# untitled.net
KiCad netlist of a schematic drawn in EAGLE
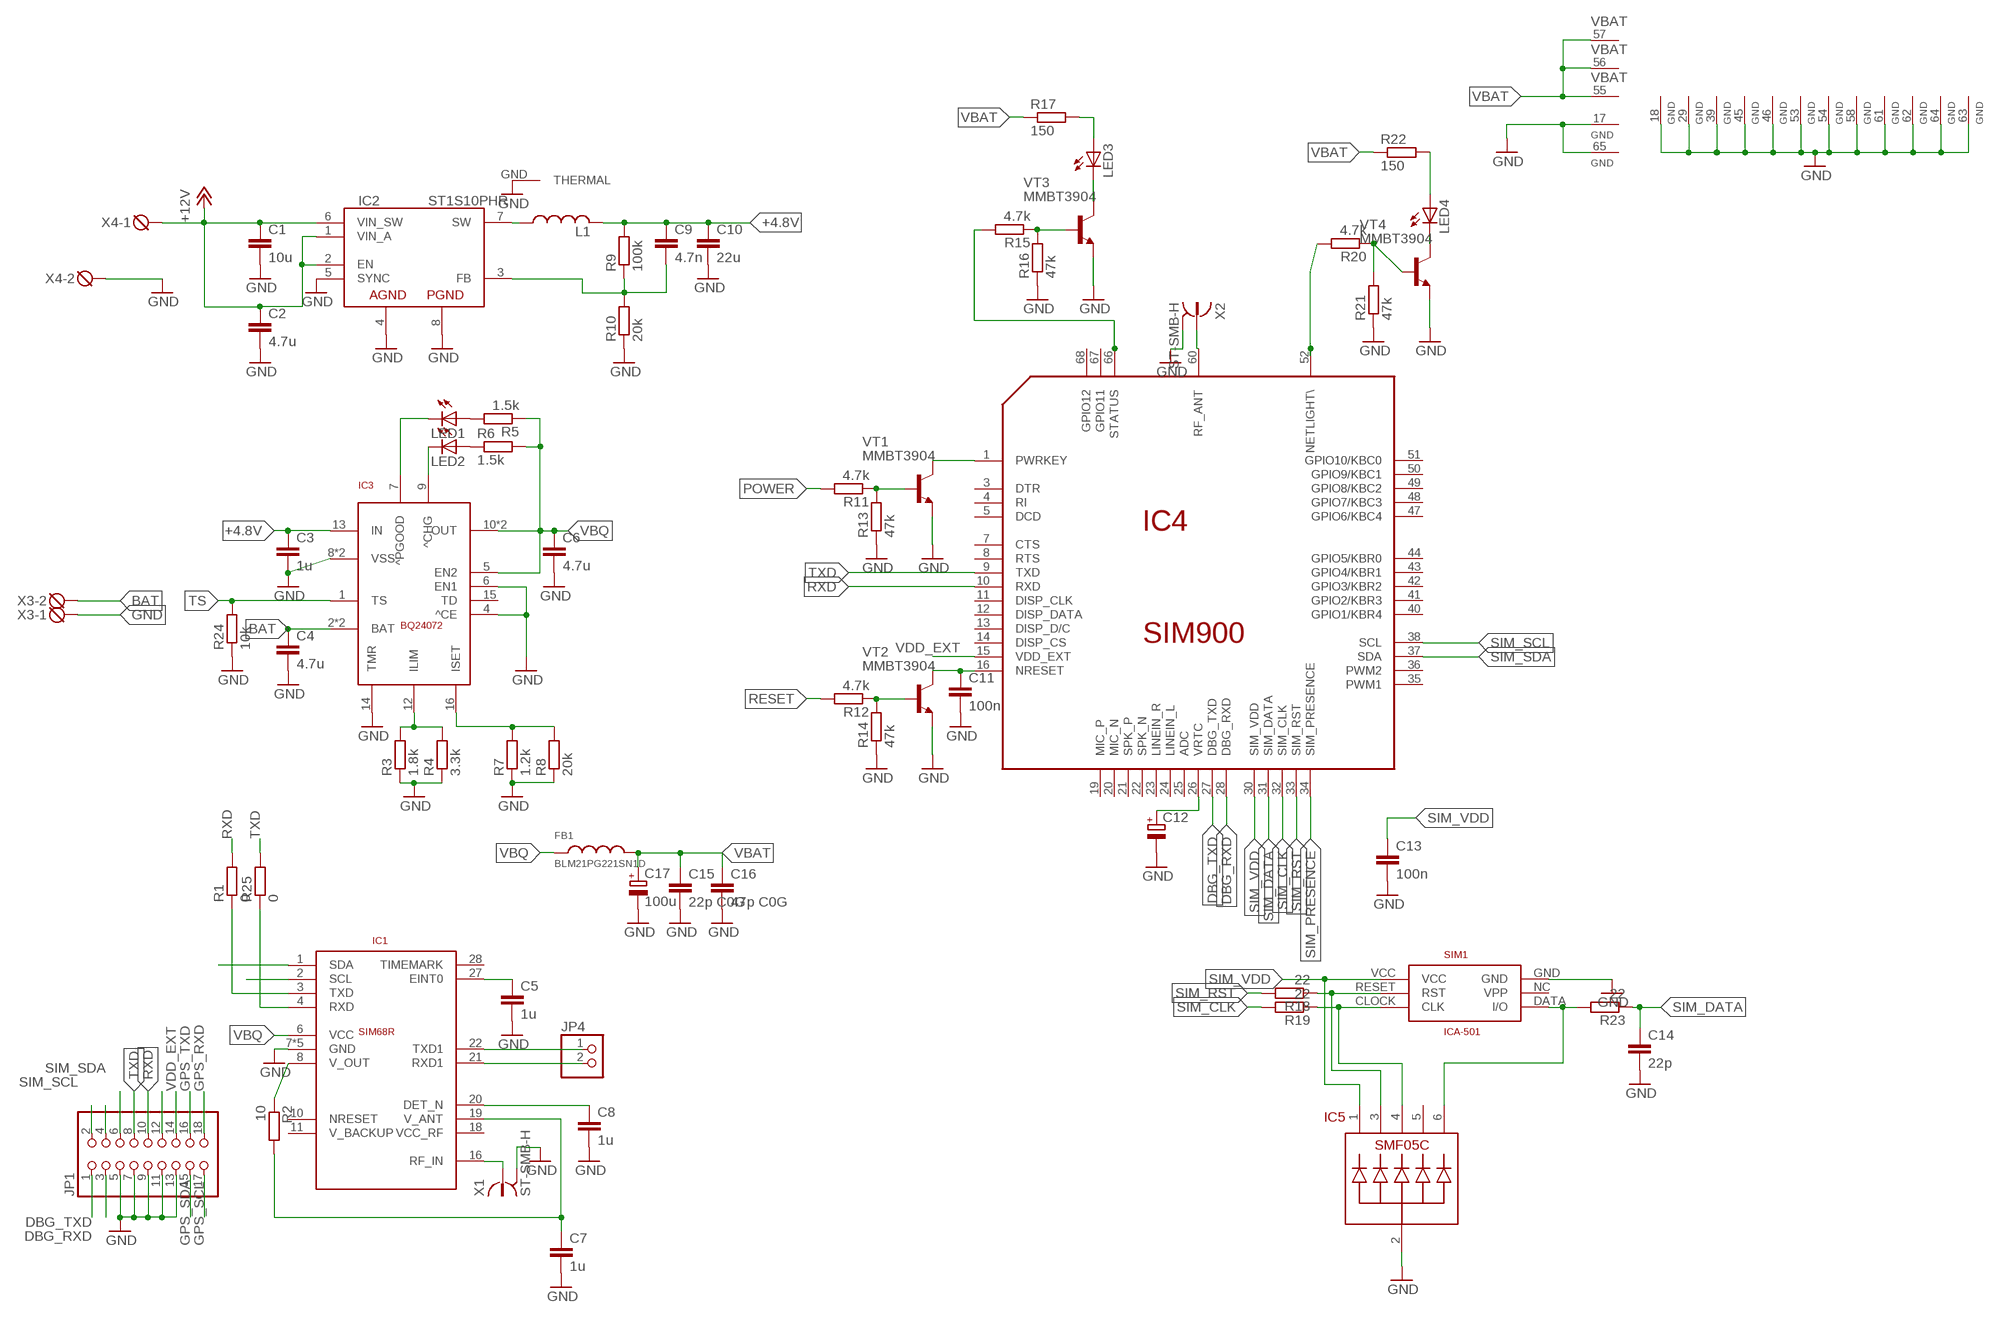
[diagram p0: schematic, sheet 1]

(export (version "E")
  (design (tool "Eeschema 10.0.6"))
  (components
    (comp (ref "C1")
      (value "10u")
      (footprint "eagle-import:C0805")
      (libsource (lib "eagle-import") (part "C-EUC0805"))
    )
    (comp (ref "C2")
      (value "4.7u")
      (footprint "eagle-import:C0805")
      (libsource (lib "eagle-import") (part "C-EUC0805"))
    )
    (comp (ref "C3")
      (value "1u")
      (footprint "eagle-import:C0805")
      (libsource (lib "eagle-import") (part "C-EUC0805"))
    )
    (comp (ref "C4")
      (value "4.7u")
      (footprint "eagle-import:C0805")
      (libsource (lib "eagle-import") (part "C-EUC0805"))
    )
    (comp (ref "C5")
      (value "1u")
      (footprint "eagle-import:C0805")
      (libsource (lib "eagle-import") (part "C-EUC0805"))
    )
    (comp (ref "C6")
      (value "4.7u")
      (footprint "eagle-import:C0805")
      (libsource (lib "eagle-import") (part "C-EUC0805"))
    )
    (comp (ref "C7")
      (value "1u")
      (footprint "eagle-import:C0805")
      (libsource (lib "eagle-import") (part "C-EUC0805"))
    )
    (comp (ref "C8")
      (value "1u")
      (footprint "eagle-import:C0805")
      (libsource (lib "eagle-import") (part "C-EUC0805"))
    )
    (comp (ref "C9")
      (value "4.7n")
      (footprint "eagle-import:C0805")
      (libsource (lib "eagle-import") (part "C-EUC0805"))
    )
    (comp (ref "C10")
      (value "22u")
      (footprint "eagle-import:C0805")
      (libsource (lib "eagle-import") (part "C-EUC0805"))
    )
    (comp (ref "C11")
      (value "100n")
      (footprint "eagle-import:C0805")
      (libsource (lib "eagle-import") (part "C-EUC0805"))
    )
    (comp (ref "C12")
      (value "CPOL-EUA/3216-18R")
      (footprint "eagle-import:A_3216-18R")
      (libsource (lib "eagle-import") (part "CPOL-EUA/3216-18R"))
    )
    (comp (ref "C13")
      (value "100n")
      (footprint "eagle-import:C0805")
      (libsource (lib "eagle-import") (part "C-EUC0805"))
    )
    (comp (ref "C14")
      (value "22p")
      (footprint "eagle-import:C0805")
      (libsource (lib "eagle-import") (part "C-EUC0805"))
    )
    (comp (ref "C15")
      (value "22p C0G")
      (footprint "eagle-import:C0805")
      (libsource (lib "eagle-import") (part "C-EUC0805"))
    )
    (comp (ref "C16")
      (value "47p C0G")
      (footprint "eagle-import:C0805")
      (libsource (lib "eagle-import") (part "C-EUC0805"))
    )
    (comp (ref "C17")
      (value "100u")
      (footprint "eagle-import:B_3528-21W")
      (libsource (lib "eagle-import") (part "CPOL-EUB/3528-21W"))
    )
    (comp (ref "FB1")
      (value "BLM21PG221SN1D")
      (footprint "eagle-import:R0805")
      (libsource (lib "eagle-import") (part "BLM21PG221"))
    )
    (comp (ref "IC1")
      (value "SIM68R")
      (footprint "eagle-import:SIM68")
      (libsource (lib "eagle-import") (part "SIM68R"))
    )
    (comp (ref "IC2")
      (value "ST1S10PHR")
      (footprint "eagle-import:HSOP8")
      (libsource (lib "eagle-import") (part "ST1S10PHR"))
    )
    (comp (ref "IC3")
      (value "BQ24072")
      (footprint "eagle-import:QFN16")
      (libsource (lib "eagle-import") (part "BQ24072"))
    )
    (comp (ref "IC4")
      (value "SIM900")
      (footprint "eagle-import:SIM900")
      (libsource (lib "eagle-import") (part "SIM900"))
    )
    (comp (ref "IC5")
      (value "SMF05C")
      (footprint "eagle-import:SC-70-6")
      (libsource (lib "eagle-import") (part "SMF05C"))
    )
    (comp (ref "JP1")
      (value "PINHD-2X9")
      (footprint "eagle-import:2X09")
      (libsource (lib "eagle-import") (part "PINHD-2X9"))
    )
    (comp (ref "JP4")
      (value "PINHD-1X2ROUND")
      (footprint "eagle-import:1X02ROUND")
      (libsource (lib "eagle-import") (part "PINHD-1X2ROUND"))
    )
    (comp (ref "L1")
      (value "INDUCTOR-SUMIDA-CDRH4D18")
      (footprint "eagle-import:INDUCTOR-SUMIDA-CDRH4D18")
      (libsource (lib "eagle-import") (part "INDUCTOR-SUMIDA-CDRH4D18"))
    )
    (comp (ref "LED1")
      (value "LED0805")
      (footprint "eagle-import:SML0805")
      (libsource (lib "eagle-import") (part "LED0805"))
    )
    (comp (ref "LED2")
      (value "LED0805")
      (footprint "eagle-import:SML0805")
      (libsource (lib "eagle-import") (part "LED0805"))
    )
    (comp (ref "LED3")
      (value "LED0805")
      (footprint "eagle-import:SML0805")
      (libsource (lib "eagle-import") (part "LED0805"))
    )
    (comp (ref "LED4")
      (value "LED0805")
      (footprint "eagle-import:SML0805")
      (libsource (lib "eagle-import") (part "LED0805"))
    )
    (comp (ref "R1")
      (value "0")
      (footprint "eagle-import:R0805")
      (libsource (lib "eagle-import") (part "R-EU_R0805"))
    )
    (comp (ref "R2")
      (value "10")
      (footprint "eagle-import:R0805")
      (libsource (lib "eagle-import") (part "R-EU_R0805"))
    )
    (comp (ref "R3")
      (value "1.8k")
      (footprint "eagle-import:R0805")
      (libsource (lib "eagle-import") (part "R-EU_R0805"))
    )
    (comp (ref "R4")
      (value "3.3k")
      (footprint "eagle-import:R0805")
      (libsource (lib "eagle-import") (part "R-EU_R0805"))
    )
    (comp (ref "R5")
      (value "1.5k")
      (footprint "eagle-import:R0603")
      (libsource (lib "eagle-import") (part "R-EU_R0603"))
    )
    (comp (ref "R6")
      (value "1.5k")
      (footprint "eagle-import:R0603")
      (libsource (lib "eagle-import") (part "R-EU_R0603"))
    )
    (comp (ref "R7")
      (value "1.2k")
      (footprint "eagle-import:R0603")
      (libsource (lib "eagle-import") (part "R-EU_R0603"))
    )
    (comp (ref "R8")
      (value "20k")
      (footprint "eagle-import:R0805")
      (libsource (lib "eagle-import") (part "R-EU_R0805"))
    )
    (comp (ref "R9")
      (value "100k")
      (footprint "eagle-import:R0805")
      (libsource (lib "eagle-import") (part "R-EU_R0805"))
    )
    (comp (ref "R10")
      (value "20k")
      (footprint "eagle-import:R0805")
      (libsource (lib "eagle-import") (part "R-EU_R0805"))
    )
    (comp (ref "R11")
      (value "4.7k")
      (footprint "eagle-import:R0805")
      (libsource (lib "eagle-import") (part "R-EU_R0805"))
    )
    (comp (ref "R12")
      (value "4.7k")
      (footprint "eagle-import:R0805")
      (libsource (lib "eagle-import") (part "R-EU_R0805"))
    )
    (comp (ref "R13")
      (value "47k")
      (footprint "eagle-import:R0805")
      (libsource (lib "eagle-import") (part "R-EU_R0805"))
    )
    (comp (ref "R14")
      (value "47k")
      (footprint "eagle-import:R0805")
      (libsource (lib "eagle-import") (part "R-EU_R0805"))
    )
    (comp (ref "R15")
      (value "4.7k")
      (footprint "eagle-import:R0805")
      (libsource (lib "eagle-import") (part "R-EU_R0805"))
    )
    (comp (ref "R16")
      (value "47k")
      (footprint "eagle-import:R0805")
      (libsource (lib "eagle-import") (part "R-EU_R0805"))
    )
    (comp (ref "R17")
      (value "150")
      (footprint "eagle-import:R0805")
      (libsource (lib "eagle-import") (part "R-EU_R0805"))
    )
    (comp (ref "R18")
      (value "22")
      (footprint "eagle-import:R0805")
      (libsource (lib "eagle-import") (part "R-EU_R0805"))
    )
    (comp (ref "R19")
      (value "22")
      (footprint "eagle-import:R0805")
      (libsource (lib "eagle-import") (part "R-EU_R0805"))
    )
    (comp (ref "R20")
      (value "4.7k")
      (footprint "eagle-import:R0805")
      (libsource (lib "eagle-import") (part "R-EU_R0805"))
    )
    (comp (ref "R21")
      (value "47k")
      (footprint "eagle-import:R0805")
      (libsource (lib "eagle-import") (part "R-EU_R0805"))
    )
    (comp (ref "R22")
      (value "150")
      (footprint "eagle-import:R0805")
      (libsource (lib "eagle-import") (part "R-EU_R0805"))
    )
    (comp (ref "R23")
      (value "22")
      (footprint "eagle-import:R0805")
      (libsource (lib "eagle-import") (part "R-EU_R0805"))
    )
    (comp (ref "R24")
      (value "10k")
      (footprint "eagle-import:R0805")
      (libsource (lib "eagle-import") (part "R-EU_R0805"))
    )
    (comp (ref "R25")
      (value "0")
      (footprint "eagle-import:R0805")
      (libsource (lib "eagle-import") (part "R-EU_R0805"))
    )
    (comp (ref "SIM1")
      (value "ICA-501")
      (footprint "eagle-import:ICA-501-006-F7")
      (libsource (lib "eagle-import") (part "ICA-501"))
    )
    (comp (ref "VT1")
      (value "MMBT3904")
      (footprint "eagle-import:SOT23-BCE")
      (libsource (lib "eagle-import") (part "MMBT3904"))
    )
    (comp (ref "VT2")
      (value "MMBT3904")
      (footprint "eagle-import:SOT23-BCE")
      (libsource (lib "eagle-import") (part "MMBT3904"))
    )
    (comp (ref "VT3")
      (value "MMBT3904")
      (footprint "eagle-import:SOT23-BCE")
      (libsource (lib "eagle-import") (part "MMBT3904"))
    )
    (comp (ref "VT4")
      (value "MMBT3904")
      (footprint "eagle-import:SOT23-BCE")
      (libsource (lib "eagle-import") (part "MMBT3904"))
    )
    (comp (ref "X1")
      (value "ST-SMB-H")
      (footprint "eagle-import:ST-SMB-H")
      (libsource (lib "eagle-import") (part "ST-SMB-H"))
    )
    (comp (ref "X2")
      (value "ST-SMB-H")
      (footprint "eagle-import:ST-SMB-H")
      (libsource (lib "eagle-import") (part "ST-SMB-H"))
    )
    (comp (ref "X3")
      (value "DG3XX-02-5.0")
      (footprint "eagle-import:DG306-5.0-02P")
      (libsource (lib "eagle-import") (part "DG3XX-02-5.0"))
    )
    (comp (ref "X4")
      (value "DG3XX-02-5.0")
      (footprint "eagle-import:DG306-5.0-02P")
      (libsource (lib "eagle-import") (part "DG3XX-02-5.0"))
    )
  )
  (nets
    (net (code "1") (name "+4.8V") (class "Default")
      (node (ref "C10") (pin "1") (pinfunction "1_1") (pintype "passive"))
      (node (ref "C3") (pin "1") (pinfunction "1_1") (pintype "passive"))
      (node (ref "C9") (pin "1") (pinfunction "1_1") (pintype "passive"))
      (node (ref "IC3") (pin "13") (pinfunction "IN_13") (pintype "bidirectional"))
      (node (ref "L1") (pin "P$2") (pinfunction "P$2_P$2") (pintype "bidirectional"))
      (node (ref "R9") (pin "2") (pinfunction "2_2") (pintype "passive"))
    )
    (net (code "2") (name "+12V") (class "Default")
      (node (ref "C1") (pin "1") (pinfunction "1_1") (pintype "passive"))
      (node (ref "C2") (pin "1") (pinfunction "1_1") (pintype "passive"))
      (node (ref "IC2") (pin "1") (pinfunction "VIN_A_1") (pintype "power_in"))
      (node (ref "IC2") (pin "2") (pinfunction "EN_2") (pintype "input"))
      (node (ref "IC2") (pin "6") (pinfunction "VIN_SW_6") (pintype "power_in"))
      (node (ref "X4") (pin "1") (pinfunction "KL_1") (pintype "passive"))
    )
    (net (code "3") (name "/GPS_RXD") (class "Default")
      (node (ref "IC1") (pin "4") (pinfunction "RXD_4") (pintype "bidirectional"))
      (node (ref "JP1") (pin "18") (pinfunction "18_18") (pintype "passive"))
      (node (ref "R25") (pin "1") (pinfunction "1_1") (pintype "passive"))
    )
    (net (code "4") (name "/GPS_SCL") (class "Default")
      (node (ref "IC1") (pin "2") (pinfunction "SCL_2") (pintype "bidirectional"))
      (node (ref "JP1") (pin "17") (pinfunction "17_17") (pintype "passive"))
    )
    (net (code "5") (name "/GPS_SDA") (class "Default")
      (node (ref "IC1") (pin "1") (pinfunction "SDA_1") (pintype "bidirectional"))
      (node (ref "JP1") (pin "15") (pinfunction "15_15") (pintype "passive"))
    )
    (net (code "6") (name "/GPS_TXD") (class "Default")
      (node (ref "IC1") (pin "3") (pinfunction "TXD_3") (pintype "bidirectional"))
      (node (ref "JP1") (pin "16") (pinfunction "16_16") (pintype "passive"))
      (node (ref "R1") (pin "1") (pinfunction "1_1") (pintype "passive"))
    )
    (net (code "7") (name "/VDD_EXT") (class "Default")
      (node (ref "IC4") (pin "15") (pinfunction "VDD_EXT_15") (pintype "bidirectional"))
      (node (ref "JP1") (pin "14") (pinfunction "14_14") (pintype "passive"))
    )
    (net (code "8") (name "BAT") (class "Default")
      (node (ref "C4") (pin "1") (pinfunction "1_1") (pintype "passive"))
      (node (ref "IC3") (pin "2") (pinfunction "BAT_2") (pintype "bidirectional"))
      (node (ref "IC3") (pin "3") (pinfunction "BAT_3") (pintype "bidirectional"))
      (node (ref "X3") (pin "2") (pinfunction "KL_2") (pintype "passive"))
    )
    (net (code "9") (name "DBG_RXD") (class "Default")
      (node (ref "IC4") (pin "28") (pinfunction "DBG_RXD_28") (pintype "bidirectional"))
      (node (ref "JP1") (pin "3") (pinfunction "3_3") (pintype "passive"))
    )
    (net (code "10") (name "DBG_TXD") (class "Default")
      (node (ref "IC4") (pin "27") (pinfunction "DBG_TXD_27") (pintype "bidirectional"))
      (node (ref "JP1") (pin "1") (pinfunction "1_1") (pintype "passive"))
    )
    (net (code "11") (name "GND") (class "Default")
      (node (ref "C1") (pin "2") (pinfunction "2_2") (pintype "passive"))
      (node (ref "C10") (pin "2") (pinfunction "2_2") (pintype "passive"))
      (node (ref "C11") (pin "2") (pinfunction "2_2") (pintype "passive"))
      (node (ref "C12") (pin "-") (pinfunction "-_-") (pintype "passive"))
      (node (ref "C13") (pin "2") (pinfunction "2_2") (pintype "passive"))
      (node (ref "C14") (pin "2") (pinfunction "2_2") (pintype "passive"))
      (node (ref "C15") (pin "2") (pinfunction "2_2") (pintype "passive"))
      (node (ref "C16") (pin "2") (pinfunction "2_2") (pintype "passive"))
      (node (ref "C17") (pin "-") (pinfunction "-_-") (pintype "passive"))
      (node (ref "C2") (pin "2") (pinfunction "2_2") (pintype "passive"))
      (node (ref "C3") (pin "2") (pinfunction "2_2") (pintype "passive"))
      (node (ref "C4") (pin "2") (pinfunction "2_2") (pintype "passive"))
      (node (ref "C5") (pin "2") (pinfunction "2_2") (pintype "passive"))
      (node (ref "C6") (pin "2") (pinfunction "2_2") (pintype "passive"))
      (node (ref "C7") (pin "2") (pinfunction "2_2") (pintype "passive"))
      (node (ref "C8") (pin "2") (pinfunction "2_2") (pintype "passive"))
      (node (ref "IC1") (pin "13") (pinfunction "GND_13") (pintype "bidirectional"))
      (node (ref "IC1") (pin "14") (pinfunction "GND_14") (pintype "bidirectional"))
      (node (ref "IC1") (pin "15") (pinfunction "GND_15") (pintype "bidirectional"))
      (node (ref "IC1") (pin "17") (pinfunction "GND_17") (pintype "bidirectional"))
      (node (ref "IC1") (pin "7") (pinfunction "GND_7") (pintype "bidirectional"))
      (node (ref "IC2") (pin "4") (pinfunction "AGND_4") (pintype "power_in"))
      (node (ref "IC2") (pin "5") (pinfunction "SYNC_5") (pintype "input"))
      (node (ref "IC2") (pin "8") (pinfunction "PGND_8") (pintype "power_in"))
      (node (ref "IC2") (pin "GND") (pinfunction "THERMAL_GND") (pintype "power_in"))
      (node (ref "IC3") (pin "14") (pinfunction "TMR_14") (pintype "bidirectional"))
      (node (ref "IC3") (pin "4") (pinfunction "^CE_4") (pintype "bidirectional"))
      (node (ref "IC3") (pin "6") (pinfunction "EN1_6") (pintype "bidirectional"))
      (node (ref "IC3") (pin "8") (pinfunction "VSS_8") (pintype "bidirectional"))
      (node (ref "IC3") (pin "TH") (pinfunction "VSS_TH") (pintype "bidirectional"))
      (node (ref "IC4") (pin "17") (pinfunction "GND_17") (pintype "power_in"))
      (node (ref "IC4") (pin "18") (pinfunction "GND_18") (pintype "power_in"))
      (node (ref "IC4") (pin "29") (pinfunction "GND_29") (pintype "power_in"))
      (node (ref "IC4") (pin "39") (pinfunction "GND_39") (pintype "power_in"))
      (node (ref "IC4") (pin "45") (pinfunction "GND_45") (pintype "power_in"))
      (node (ref "IC4") (pin "46") (pinfunction "GND_46") (pintype "power_in"))
      (node (ref "IC4") (pin "53") (pinfunction "GND_53") (pintype "power_in"))
      (node (ref "IC4") (pin "54") (pinfunction "GND_54") (pintype "power_in"))
      (node (ref "IC4") (pin "58") (pinfunction "GND_58") (pintype "power_in"))
      (node (ref "IC4") (pin "61") (pinfunction "GND_61") (pintype "power_in"))
      (node (ref "IC4") (pin "62") (pinfunction "GND_62") (pintype "power_in"))
      (node (ref "IC4") (pin "63") (pinfunction "GND_63") (pintype "power_in"))
      (node (ref "IC4") (pin "64") (pinfunction "GND_64") (pintype "power_in"))
      (node (ref "IC4") (pin "65") (pinfunction "GND_65") (pintype "power_in"))
      (node (ref "IC5") (pin "2") (pinfunction "2_2") (pintype "bidirectional"))
      (node (ref "JP1") (pin "11") (pinfunction "11_11") (pintype "passive"))
      (node (ref "JP1") (pin "13") (pinfunction "13_13") (pintype "passive"))
      (node (ref "JP1") (pin "5") (pinfunction "5_5") (pintype "passive"))
      (node (ref "JP1") (pin "7") (pinfunction "7_7") (pintype "passive"))
      (node (ref "JP1") (pin "9") (pinfunction "9_9") (pintype "passive"))
      (node (ref "R10") (pin "1") (pinfunction "1_1") (pintype "passive"))
      (node (ref "R13") (pin "1") (pinfunction "1_1") (pintype "passive"))
      (node (ref "R14") (pin "1") (pinfunction "1_1") (pintype "passive"))
      (node (ref "R16") (pin "1") (pinfunction "1_1") (pintype "passive"))
      (node (ref "R21") (pin "1") (pinfunction "1_1") (pintype "passive"))
      (node (ref "R24") (pin "1") (pinfunction "1_1") (pintype "passive"))
      (node (ref "R3") (pin "1") (pinfunction "1_1") (pintype "passive"))
      (node (ref "R4") (pin "1") (pinfunction "1_1") (pintype "passive"))
      (node (ref "R7") (pin "1") (pinfunction "1_1") (pintype "passive"))
      (node (ref "R8") (pin "1") (pinfunction "1_1") (pintype "passive"))
      (node (ref "SIM1") (pin "GND") (pinfunction "GND_GND") (pintype "bidirectional"))
      (node (ref "VT1") (pin "E") (pinfunction "E_E") (pintype "passive"))
      (node (ref "VT2") (pin "E") (pinfunction "E_E") (pintype "passive"))
      (node (ref "VT3") (pin "E") (pinfunction "E_E") (pintype "passive"))
      (node (ref "VT4") (pin "E") (pinfunction "E_E") (pintype "passive"))
      (node (ref "X1") (pin "2") (pinfunction "2_2") (pintype "passive"))
      (node (ref "X1") (pin "3") (pinfunction "2_3") (pintype "passive"))
      (node (ref "X1") (pin "4") (pinfunction "2_4") (pintype "passive"))
      (node (ref "X1") (pin "5") (pinfunction "2_5") (pintype "passive"))
      (node (ref "X2") (pin "2") (pinfunction "2_2") (pintype "passive"))
      (node (ref "X2") (pin "3") (pinfunction "2_3") (pintype "passive"))
      (node (ref "X2") (pin "4") (pinfunction "2_4") (pintype "passive"))
      (node (ref "X2") (pin "5") (pinfunction "2_5") (pintype "passive"))
      (node (ref "X3") (pin "1") (pinfunction "KL_1") (pintype "passive"))
      (node (ref "X4") (pin "2") (pinfunction "KL_2") (pintype "passive"))
    )
    (net (code "12") (name "Net-(IC1-DET_N)") (class "Default")
      (node (ref "C8") (pin "1") (pinfunction "1_1") (pintype "passive"))
      (node (ref "IC1") (pin "20") (pinfunction "DET_N_20") (pintype "bidirectional"))
    )
    (net (code "13") (name "Net-(IC1-EINT0)") (class "Default")
      (node (ref "C5") (pin "1") (pinfunction "1_1") (pintype "passive"))
      (node (ref "IC1") (pin "27") (pinfunction "EINT0_27") (pintype "bidirectional"))
    )
    (net (code "14") (name "Net-(IC1-RF_IN)") (class "Default")
      (node (ref "IC1") (pin "16") (pinfunction "RF_IN_16") (pintype "bidirectional"))
      (node (ref "X1") (pin "1") (pinfunction "1_1") (pintype "passive"))
    )
    (net (code "15") (name "Net-(IC1-RXD1)") (class "Default")
      (node (ref "IC1") (pin "21") (pinfunction "RXD1_21") (pintype "bidirectional"))
      (node (ref "JP4") (pin "2") (pinfunction "2_2") (pintype "passive"))
    )
    (net (code "16") (name "Net-(IC1-TXD1)") (class "Default")
      (node (ref "IC1") (pin "22") (pinfunction "TXD1_22") (pintype "bidirectional"))
      (node (ref "JP4") (pin "1") (pinfunction "1_1") (pintype "passive"))
    )
    (net (code "17") (name "Net-(IC1-V_ANT)") (class "Default")
      (node (ref "C7") (pin "1") (pinfunction "1_1") (pintype "passive"))
      (node (ref "IC1") (pin "19") (pinfunction "V_ANT_19") (pintype "bidirectional"))
      (node (ref "R2") (pin "2") (pinfunction "2_2") (pintype "passive"))
    )
    (net (code "18") (name "Net-(IC1-V_OUT)") (class "Default")
      (node (ref "IC1") (pin "8") (pinfunction "V_OUT_8") (pintype "bidirectional"))
      (node (ref "R2") (pin "1") (pinfunction "1_1") (pintype "passive"))
    )
    (net (code "19") (name "Net-(IC2A-FB)") (class "Default")
      (node (ref "C9") (pin "2") (pinfunction "2_2") (pintype "passive"))
      (node (ref "IC2") (pin "3") (pinfunction "FB_3") (pintype "input"))
      (node (ref "R10") (pin "2") (pinfunction "2_2") (pintype "passive"))
      (node (ref "R9") (pin "1") (pinfunction "1_1") (pintype "passive"))
    )
    (net (code "20") (name "Net-(IC2A-SW)") (class "Default")
      (node (ref "IC2") (pin "7") (pinfunction "SW_7") (pintype "output"))
      (node (ref "L1") (pin "P$1") (pinfunction "P$1_P$1") (pintype "bidirectional"))
    )
    (net (code "21") (name "Net-(IC3-ILIM)") (class "Default")
      (node (ref "IC3") (pin "12") (pinfunction "ILIM_12") (pintype "bidirectional"))
      (node (ref "R3") (pin "2") (pinfunction "2_2") (pintype "passive"))
      (node (ref "R4") (pin "2") (pinfunction "2_2") (pintype "passive"))
    )
    (net (code "22") (name "Net-(IC3-ISET)") (class "Default")
      (node (ref "IC3") (pin "16") (pinfunction "ISET_16") (pintype "bidirectional"))
      (node (ref "R7") (pin "2") (pinfunction "2_2") (pintype "passive"))
      (node (ref "R8") (pin "2") (pinfunction "2_2") (pintype "passive"))
    )
    (net (code "23") (name "Net-(IC3-^CHG)") (class "Default")
      (node (ref "IC3") (pin "9") (pinfunction "^CHG_9") (pintype "bidirectional"))
      (node (ref "LED2") (pin "C") (pinfunction "C_C") (pintype "passive"))
    )
    (net (code "24") (name "Net-(IC3-^PGOOD)") (class "Default")
      (node (ref "IC3") (pin "7") (pinfunction "^PGOOD_7") (pintype "bidirectional"))
      (node (ref "LED1") (pin "C") (pinfunction "C_C") (pintype "passive"))
    )
    (net (code "25") (name "Net-(IC4A-NETLIGHT\\)") (class "Default")
      (node (ref "IC4") (pin "52") (pinfunction "NETLIGHT\\_52") (pintype "bidirectional"))
      (node (ref "R20") (pin "2") (pinfunction "2_2") (pintype "passive"))
    )
    (net (code "26") (name "Net-(IC4A-NRESET)") (class "Default")
      (node (ref "C11") (pin "1") (pinfunction "1_1") (pintype "passive"))
      (node (ref "IC4") (pin "16") (pinfunction "NRESET_16") (pintype "bidirectional"))
      (node (ref "VT2") (pin "C") (pinfunction "C_C") (pintype "passive"))
    )
    (net (code "27") (name "Net-(IC4A-PWRKEY)") (class "Default")
      (node (ref "IC4") (pin "1") (pinfunction "PWRKEY_1") (pintype "bidirectional"))
      (node (ref "VT1") (pin "C") (pinfunction "C_C") (pintype "passive"))
    )
    (net (code "28") (name "Net-(IC4A-RF_ANT)") (class "Default")
      (node (ref "IC4") (pin "60") (pinfunction "RF_ANT_60") (pintype "bidirectional"))
      (node (ref "X2") (pin "1") (pinfunction "1_1") (pintype "passive"))
    )
    (net (code "29") (name "Net-(IC4A-STATUS)") (class "Default")
      (node (ref "IC4") (pin "66") (pinfunction "STATUS_66") (pintype "bidirectional"))
      (node (ref "R15") (pin "2") (pinfunction "2_2") (pintype "passive"))
    )
    (net (code "30") (name "Net-(IC4A-VRTC)") (class "Default")
      (node (ref "C12") (pin "+") (pinfunction "+_+") (pintype "passive"))
      (node (ref "IC4") (pin "26") (pinfunction "VRTC_26") (pintype "bidirectional"))
    )
    (net (code "31") (name "Net-(LED1-PadA)") (class "Default")
      (node (ref "LED1") (pin "A") (pinfunction "A_A") (pintype "passive"))
      (node (ref "R5") (pin "2") (pinfunction "2_2") (pintype "passive"))
    )
    (net (code "32") (name "Net-(LED2-PadA)") (class "Default")
      (node (ref "LED2") (pin "A") (pinfunction "A_A") (pintype "passive"))
      (node (ref "R6") (pin "1") (pinfunction "1_1") (pintype "passive"))
    )
    (net (code "33") (name "Net-(LED3-PadA)") (class "Default")
      (node (ref "LED3") (pin "A") (pinfunction "A_A") (pintype "passive"))
      (node (ref "R17") (pin "2") (pinfunction "2_2") (pintype "passive"))
    )
    (net (code "34") (name "Net-(LED3-PadC)") (class "Default")
      (node (ref "LED3") (pin "C") (pinfunction "C_C") (pintype "passive"))
      (node (ref "VT3") (pin "C") (pinfunction "C_C") (pintype "passive"))
    )
    (net (code "35") (name "Net-(LED4-PadA)") (class "Default")
      (node (ref "LED4") (pin "A") (pinfunction "A_A") (pintype "passive"))
      (node (ref "R22") (pin "2") (pinfunction "2_2") (pintype "passive"))
    )
    (net (code "36") (name "Net-(LED4-PadC)") (class "Default")
      (node (ref "LED4") (pin "C") (pinfunction "C_C") (pintype "passive"))
      (node (ref "VT4") (pin "C") (pinfunction "C_C") (pintype "passive"))
    )
    (net (code "37") (name "Net-(R11-Pad1)") (class "Default")
      (node (ref "R11") (pin "1") (pinfunction "1_1") (pintype "passive"))
      (node (ref "R13") (pin "2") (pinfunction "2_2") (pintype "passive"))
      (node (ref "VT1") (pin "B") (pinfunction "B_B") (pintype "passive"))
    )
    (net (code "38") (name "Net-(R12-Pad1)") (class "Default")
      (node (ref "R12") (pin "1") (pinfunction "1_1") (pintype "passive"))
      (node (ref "R14") (pin "2") (pinfunction "2_2") (pintype "passive"))
      (node (ref "VT2") (pin "B") (pinfunction "B_B") (pintype "passive"))
    )
    (net (code "39") (name "Net-(R15-Pad1)") (class "Default")
      (node (ref "R15") (pin "1") (pinfunction "1_1") (pintype "passive"))
      (node (ref "R16") (pin "2") (pinfunction "2_2") (pintype "passive"))
      (node (ref "VT3") (pin "B") (pinfunction "B_B") (pintype "passive"))
    )
    (net (code "40") (name "Net-(R20-Pad1)") (class "Default")
      (node (ref "R20") (pin "1") (pinfunction "1_1") (pintype "passive"))
      (node (ref "R21") (pin "2") (pinfunction "2_2") (pintype "passive"))
      (node (ref "VT4") (pin "B") (pinfunction "B_B") (pintype "passive"))
    )
    (net (code "41") (name "Net-(SIM1-CLK)") (class "Default")
      (node (ref "IC5") (pin "4") (pinfunction "4_4") (pintype "bidirectional"))
      (node (ref "R19") (pin "1") (pinfunction "1_1") (pintype "passive"))
      (node (ref "SIM1") (pin "CLOCK") (pinfunction "CLK_CLOCK") (pintype "bidirectional"))
    )
    (net (code "42") (name "Net-(SIM1-I{slash}O)") (class "Default")
      (node (ref "IC5") (pin "6") (pinfunction "6_6") (pintype "bidirectional"))
      (node (ref "R23") (pin "2") (pinfunction "2_2") (pintype "passive"))
      (node (ref "SIM1") (pin "DATA") (pinfunction "I/O_DATA") (pintype "bidirectional"))
    )
    (net (code "43") (name "Net-(SIM1-RST)") (class "Default")
      (node (ref "IC5") (pin "3") (pinfunction "3_3") (pintype "bidirectional"))
      (node (ref "R18") (pin "1") (pinfunction "1_1") (pintype "passive"))
      (node (ref "SIM1") (pin "RESET") (pinfunction "RST_RESET") (pintype "bidirectional"))
    )
    (net (code "44") (name "POWER") (class "Default")
      (node (ref "JP1") (pin "12") (pinfunction "12_12") (pintype "passive"))
      (node (ref "R11") (pin "2") (pinfunction "2_2") (pintype "passive"))
    )
    (net (code "45") (name "RESET") (class "Default")
      (node (ref "JP1") (pin "6") (pinfunction "6_6") (pintype "passive"))
      (node (ref "R12") (pin "2") (pinfunction "2_2") (pintype "passive"))
    )
    (net (code "46") (name "RXD") (class "Default")
      (node (ref "IC4") (pin "10") (pinfunction "RXD_10") (pintype "bidirectional"))
      (node (ref "JP1") (pin "10") (pinfunction "10_10") (pintype "passive"))
      (node (ref "R1") (pin "2") (pinfunction "2_2") (pintype "passive"))
    )
    (net (code "47") (name "SIM_CLK") (class "Default")
      (node (ref "IC4") (pin "32") (pinfunction "SIM_CLK_32") (pintype "bidirectional"))
      (node (ref "R19") (pin "2") (pinfunction "2_2") (pintype "passive"))
    )
    (net (code "48") (name "SIM_DATA") (class "Default")
      (node (ref "C14") (pin "1") (pinfunction "1_1") (pintype "passive"))
      (node (ref "IC4") (pin "31") (pinfunction "SIM_DATA_31") (pintype "bidirectional"))
      (node (ref "R23") (pin "1") (pinfunction "1_1") (pintype "passive"))
    )
    (net (code "49") (name "SIM_PRESENCE") (class "Default")
      (node (ref "IC4") (pin "34") (pinfunction "SIM_PRESENCE_34") (pintype "bidirectional"))
    )
    (net (code "50") (name "SIM_RST") (class "Default")
      (node (ref "IC4") (pin "33") (pinfunction "SIM_RST_33") (pintype "bidirectional"))
      (node (ref "R18") (pin "2") (pinfunction "2_2") (pintype "passive"))
    )
    (net (code "51") (name "SIM_SCL") (class "Default")
      (node (ref "IC4") (pin "38") (pinfunction "SCL_38") (pintype "bidirectional"))
      (node (ref "JP1") (pin "2") (pinfunction "2_2") (pintype "passive"))
    )
    (net (code "52") (name "SIM_SDA") (class "Default")
      (node (ref "IC4") (pin "37") (pinfunction "SDA_37") (pintype "bidirectional"))
      (node (ref "JP1") (pin "4") (pinfunction "4_4") (pintype "passive"))
    )
    (net (code "53") (name "SIM_VDD") (class "Default")
      (node (ref "C13") (pin "1") (pinfunction "1_1") (pintype "passive"))
      (node (ref "IC4") (pin "30") (pinfunction "SIM_VDD_30") (pintype "bidirectional"))
      (node (ref "IC5") (pin "1") (pinfunction "1_1") (pintype "bidirectional"))
      (node (ref "SIM1") (pin "VCC") (pinfunction "VCC_VCC") (pintype "bidirectional"))
    )
    (net (code "54") (name "TS") (class "Default")
      (node (ref "IC3") (pin "1") (pinfunction "TS_1") (pintype "bidirectional"))
      (node (ref "R24") (pin "2") (pinfunction "2_2") (pintype "passive"))
    )
    (net (code "55") (name "TXD") (class "Default")
      (node (ref "IC4") (pin "9") (pinfunction "TXD_9") (pintype "bidirectional"))
      (node (ref "JP1") (pin "8") (pinfunction "8_8") (pintype "passive"))
      (node (ref "R25") (pin "2") (pinfunction "2_2") (pintype "passive"))
    )
    (net (code "56") (name "VBAT") (class "Default")
      (node (ref "C15") (pin "1") (pinfunction "1_1") (pintype "passive"))
      (node (ref "C16") (pin "1") (pinfunction "1_1") (pintype "passive"))
      (node (ref "C17") (pin "+") (pinfunction "+_+") (pintype "passive"))
      (node (ref "FB1") (pin "2") (pinfunction "2_2") (pintype "passive"))
      (node (ref "IC4") (pin "55") (pinfunction "VBAT_55") (pintype "power_in"))
      (node (ref "IC4") (pin "56") (pinfunction "VBAT_56") (pintype "power_in"))
      (node (ref "IC4") (pin "57") (pinfunction "VBAT_57") (pintype "power_in"))
      (node (ref "R17") (pin "1") (pinfunction "1_1") (pintype "passive"))
      (node (ref "R22") (pin "1") (pinfunction "1_1") (pintype "passive"))
    )
    (net (code "57") (name "VBQ") (class "Default")
      (node (ref "C6") (pin "1") (pinfunction "1_1") (pintype "passive"))
      (node (ref "FB1") (pin "1") (pinfunction "1_1") (pintype "passive"))
      (node (ref "IC1") (pin "6") (pinfunction "VCC_6") (pintype "bidirectional"))
      (node (ref "IC3") (pin "10") (pinfunction "OUT_10") (pintype "bidirectional"))
      (node (ref "IC3") (pin "11") (pinfunction "OUT_11") (pintype "bidirectional"))
      (node (ref "IC3") (pin "5") (pinfunction "EN2_5") (pintype "bidirectional"))
      (node (ref "R5") (pin "1") (pinfunction "1_1") (pintype "passive"))
      (node (ref "R6") (pin "2") (pinfunction "2_2") (pintype "passive"))
    )
    (net (code "58") (name "unconnected-(IC1-NRESET-Pad10)") (class "Default")
      (node (ref "IC1") (pin "10") (pinfunction "NRESET_10") (pintype "bidirectional"))
    )
    (net (code "59") (name "unconnected-(IC1-TIMEMARK-Pad28)") (class "Default")
      (node (ref "IC1") (pin "28") (pinfunction "TIMEMARK_28") (pintype "bidirectional"))
    )
    (net (code "60") (name "unconnected-(IC1-VCC_RF-Pad18)") (class "Default")
      (node (ref "IC1") (pin "18") (pinfunction "VCC_RF_18") (pintype "bidirectional"))
    )
    (net (code "61") (name "unconnected-(IC1-V_BACKUP-Pad11)") (class "Default")
      (node (ref "IC1") (pin "11") (pinfunction "V_BACKUP_11") (pintype "bidirectional"))
    )
    (net (code "62") (name "unconnected-(IC3-TD-Pad15)") (class "Default")
      (node (ref "IC3") (pin "15") (pinfunction "TD_15") (pintype "bidirectional"))
    )
    (net (code "63") (name "unconnected-(IC4A-ADC-Pad25)") (class "Default")
      (node (ref "IC4") (pin "25") (pinfunction "ADC_25") (pintype "bidirectional"))
    )
    (net (code "64") (name "unconnected-(IC4A-CTS-Pad7)") (class "Default")
      (node (ref "IC4") (pin "7") (pinfunction "CTS_7") (pintype "bidirectional"))
    )
    (net (code "65") (name "unconnected-(IC4A-DCD-Pad5)") (class "Default")
      (node (ref "IC4") (pin "5") (pinfunction "DCD_5") (pintype "bidirectional"))
    )
    (net (code "66") (name "unconnected-(IC4A-DISP_CLK-Pad11)") (class "Default")
      (node (ref "IC4") (pin "11") (pinfunction "DISP_CLK_11") (pintype "bidirectional"))
    )
    (net (code "67") (name "unconnected-(IC4A-DISP_CS-Pad14)") (class "Default")
      (node (ref "IC4") (pin "14") (pinfunction "DISP_CS_14") (pintype "bidirectional"))
    )
    (net (code "68") (name "unconnected-(IC4A-DISP_DATA-Pad12)") (class "Default")
      (node (ref "IC4") (pin "12") (pinfunction "DISP_DATA_12") (pintype "bidirectional"))
    )
    (net (code "69") (name "unconnected-(IC4A-DISP_D{slash}C-Pad13)") (class "Default")
      (node (ref "IC4") (pin "13") (pinfunction "DISP_D/C_13") (pintype "bidirectional"))
    )
    (net (code "70") (name "unconnected-(IC4A-DTR-Pad3)") (class "Default")
      (node (ref "IC4") (pin "3") (pinfunction "DTR_3") (pintype "bidirectional"))
    )
    (net (code "71") (name "unconnected-(IC4A-GPIO1{slash}KBR4-Pad40)") (class "Default")
      (node (ref "IC4") (pin "40") (pinfunction "GPIO1/KBR4_40") (pintype "bidirectional"))
    )
    (net (code "72") (name "unconnected-(IC4A-GPIO2{slash}KBR3-Pad41)") (class "Default")
      (node (ref "IC4") (pin "41") (pinfunction "GPIO2/KBR3_41") (pintype "bidirectional"))
    )
    (net (code "73") (name "unconnected-(IC4A-GPIO3{slash}KBR2-Pad42)") (class "Default")
      (node (ref "IC4") (pin "42") (pinfunction "GPIO3/KBR2_42") (pintype "bidirectional"))
    )
    (net (code "74") (name "unconnected-(IC4A-GPIO4{slash}KBR1-Pad43)") (class "Default")
      (node (ref "IC4") (pin "43") (pinfunction "GPIO4/KBR1_43") (pintype "bidirectional"))
    )
    (net (code "75") (name "unconnected-(IC4A-GPIO5{slash}KBR0-Pad44)") (class "Default")
      (node (ref "IC4") (pin "44") (pinfunction "GPIO5/KBR0_44") (pintype "bidirectional"))
    )
    (net (code "76") (name "unconnected-(IC4A-GPIO6{slash}KBC4-Pad47)") (class "Default")
      (node (ref "IC4") (pin "47") (pinfunction "GPIO6/KBC4_47") (pintype "bidirectional"))
    )
    (net (code "77") (name "unconnected-(IC4A-GPIO7{slash}KBC3-Pad48)") (class "Default")
      (node (ref "IC4") (pin "48") (pinfunction "GPIO7/KBC3_48") (pintype "bidirectional"))
    )
    (net (code "78") (name "unconnected-(IC4A-GPIO8{slash}KBC2-Pad49)") (class "Default")
      (node (ref "IC4") (pin "49") (pinfunction "GPIO8/KBC2_49") (pintype "bidirectional"))
    )
    (net (code "79") (name "unconnected-(IC4A-GPIO9{slash}KBC1-Pad50)") (class "Default")
      (node (ref "IC4") (pin "50") (pinfunction "GPIO9/KBC1_50") (pintype "bidirectional"))
    )
    (net (code "80") (name "unconnected-(IC4A-GPIO10{slash}KBC0-Pad51)") (class "Default")
      (node (ref "IC4") (pin "51") (pinfunction "GPIO10/KBC0_51") (pintype "bidirectional"))
    )
    (net (code "81") (name "unconnected-(IC4A-GPIO11-Pad67)") (class "Default")
      (node (ref "IC4") (pin "67") (pinfunction "GPIO11_67") (pintype "bidirectional"))
    )
    (net (code "82") (name "unconnected-(IC4A-GPIO12-Pad68)") (class "Default")
      (node (ref "IC4") (pin "68") (pinfunction "GPIO12_68") (pintype "bidirectional"))
    )
    (net (code "83") (name "unconnected-(IC4A-LINEIN_L-Pad24)") (class "Default")
      (node (ref "IC4") (pin "24") (pinfunction "LINEIN_L_24") (pintype "bidirectional"))
    )
    (net (code "84") (name "unconnected-(IC4A-LINEIN_R-Pad23)") (class "Default")
      (node (ref "IC4") (pin "23") (pinfunction "LINEIN_R_23") (pintype "bidirectional"))
    )
    (net (code "85") (name "unconnected-(IC4A-MIC_N-Pad20)") (class "Default")
      (node (ref "IC4") (pin "20") (pinfunction "MIC_N_20") (pintype "bidirectional"))
    )
    (net (code "86") (name "unconnected-(IC4A-MIC_P-Pad19)") (class "Default")
      (node (ref "IC4") (pin "19") (pinfunction "MIC_P_19") (pintype "bidirectional"))
    )
    (net (code "87") (name "unconnected-(IC4A-PWM1-Pad35)") (class "Default")
      (node (ref "IC4") (pin "35") (pinfunction "PWM1_35") (pintype "bidirectional"))
    )
    (net (code "88") (name "unconnected-(IC4A-PWM2-Pad36)") (class "Default")
      (node (ref "IC4") (pin "36") (pinfunction "PWM2_36") (pintype "bidirectional"))
    )
    (net (code "89") (name "unconnected-(IC4A-RI-Pad4)") (class "Default")
      (node (ref "IC4") (pin "4") (pinfunction "RI_4") (pintype "bidirectional"))
    )
    (net (code "90") (name "unconnected-(IC4A-RTS-Pad8)") (class "Default")
      (node (ref "IC4") (pin "8") (pinfunction "RTS_8") (pintype "bidirectional"))
    )
    (net (code "91") (name "unconnected-(IC4A-SPK_N-Pad22)") (class "Default")
      (node (ref "IC4") (pin "22") (pinfunction "SPK_N_22") (pintype "bidirectional"))
    )
    (net (code "92") (name "unconnected-(IC4A-SPK_P-Pad21)") (class "Default")
      (node (ref "IC4") (pin "21") (pinfunction "SPK_P_21") (pintype "bidirectional"))
    )
    (net (code "93") (name "unconnected-(IC5-Pad5)") (class "Default")
      (node (ref "IC5") (pin "5") (pinfunction "5_5") (pintype "bidirectional"))
    )
    (net (code "94") (name "unconnected-(SIM1-VPP-PadNC)") (class "Default")
      (node (ref "SIM1") (pin "NC") (pinfunction "VPP_NC") (pintype "bidirectional"))
    )
  )
)
